# MM_Main.net
KiCad netlist of a schematic drawn in EAGLE
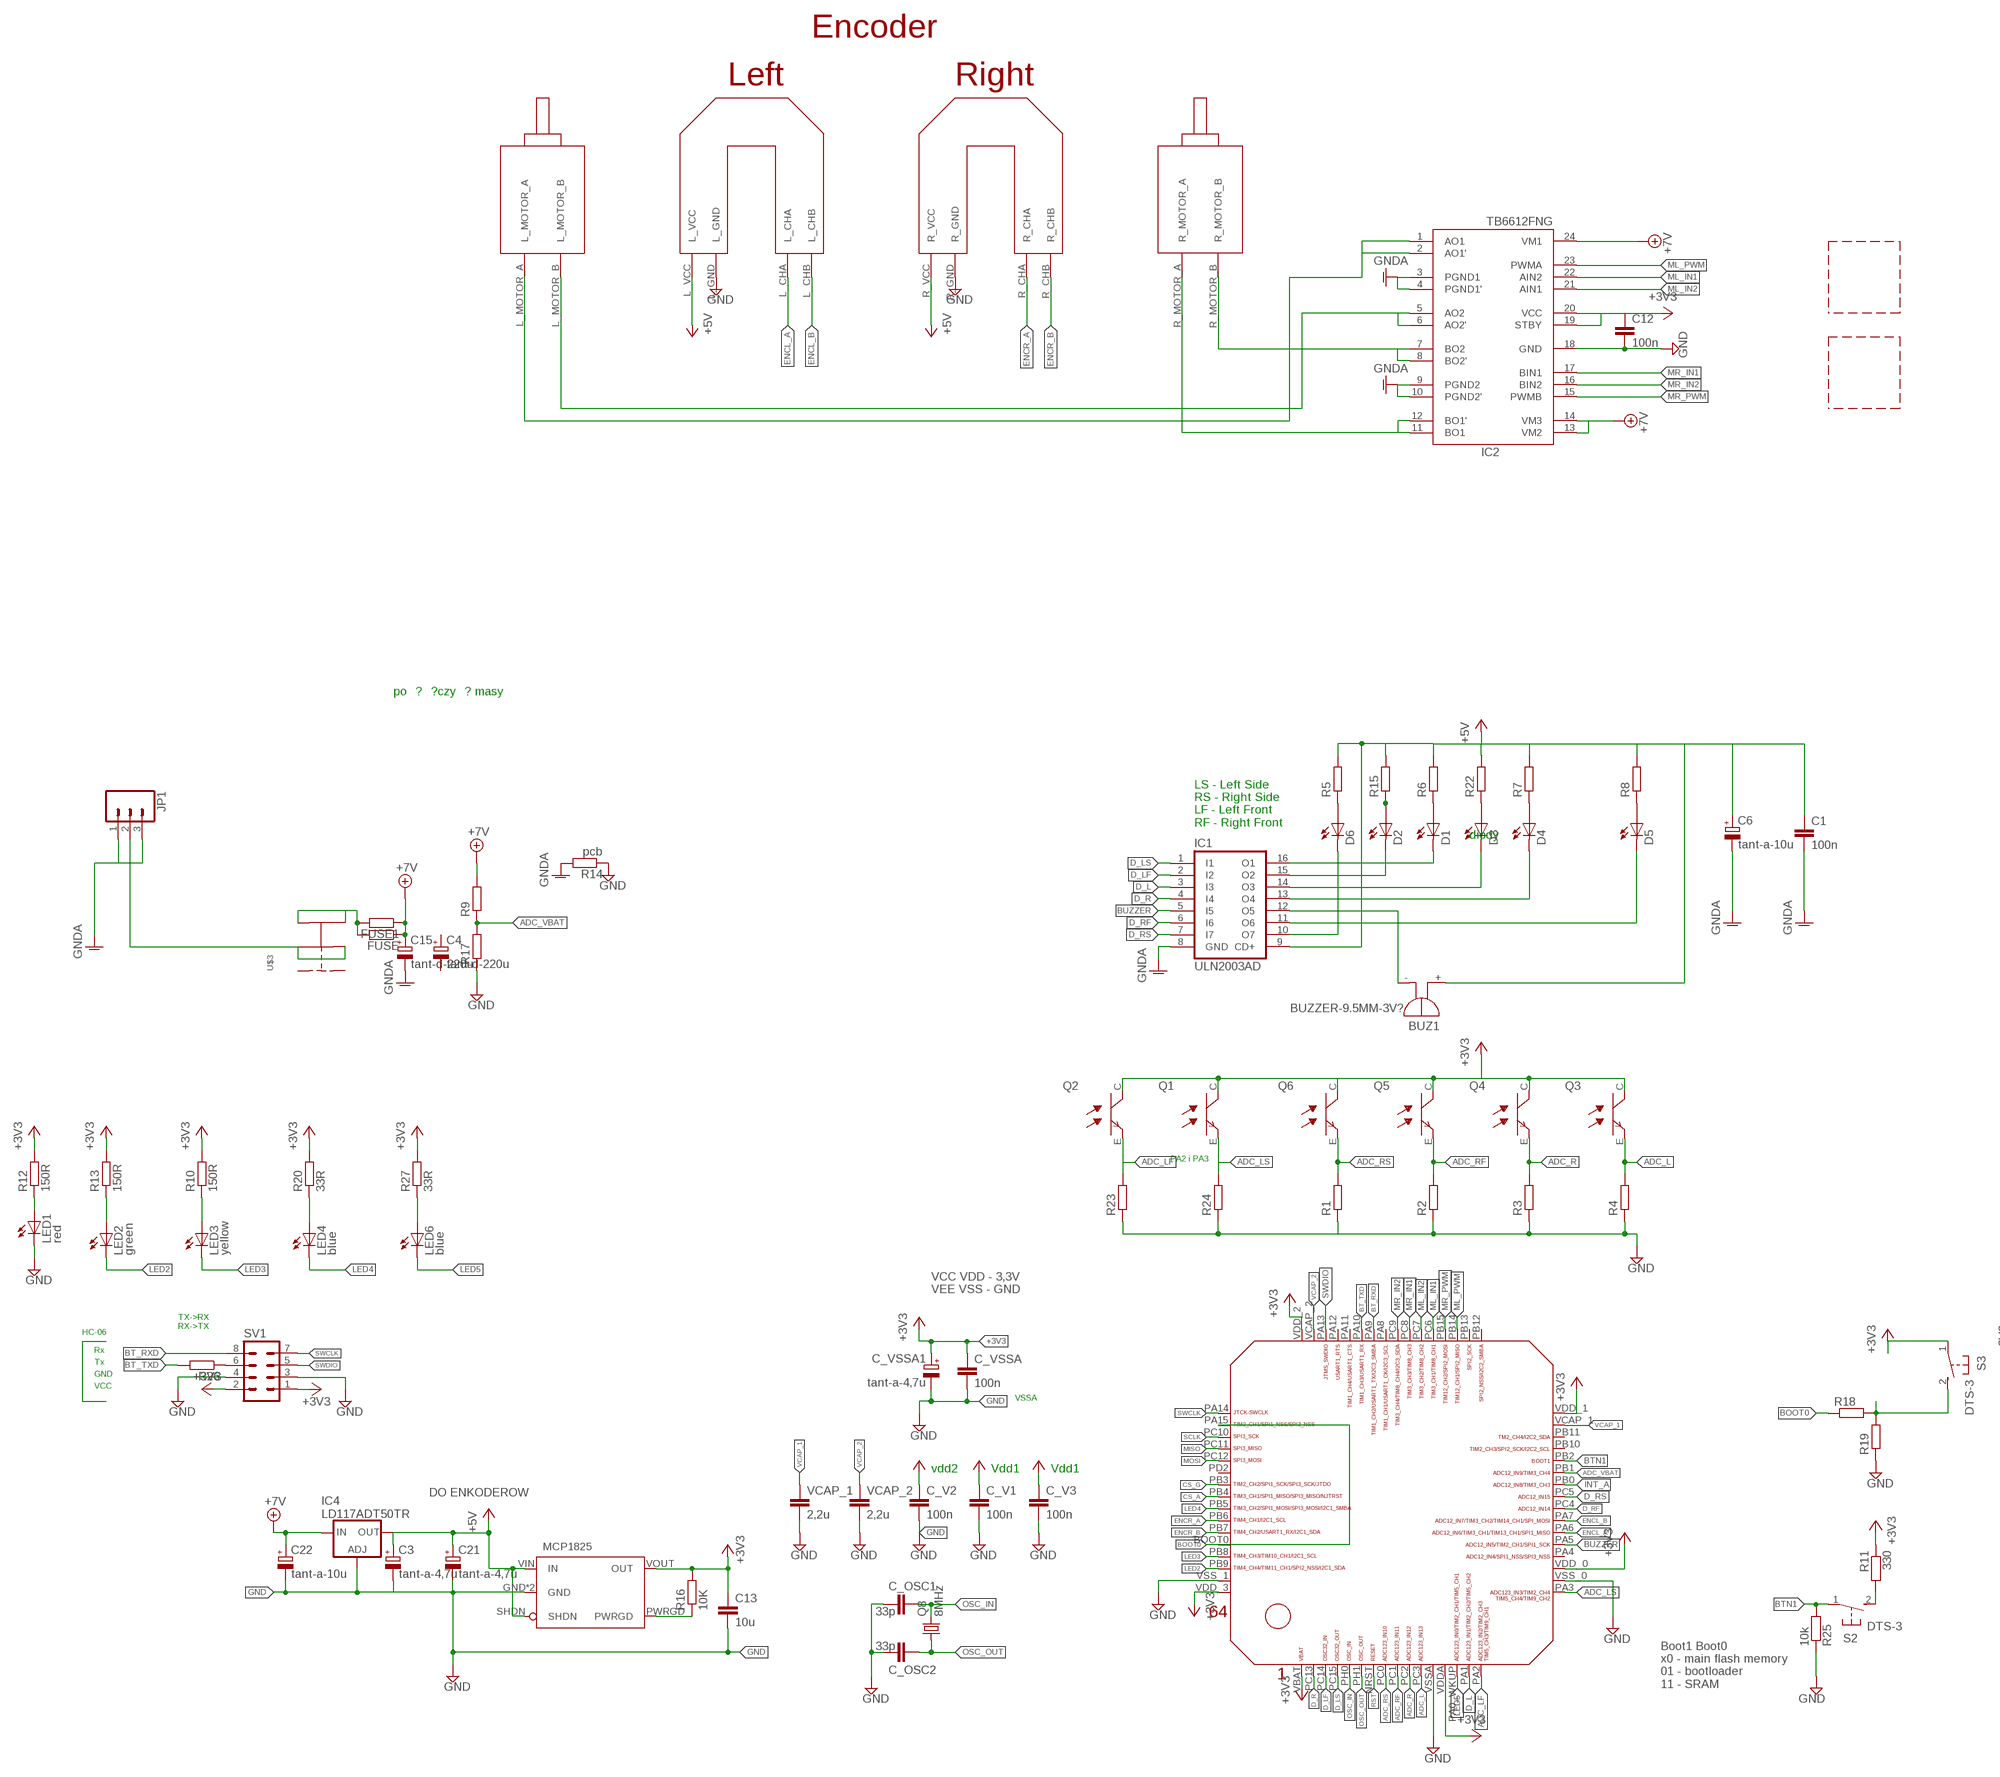
[diagram p0: schematic, sheet 1, part 1 of 2]
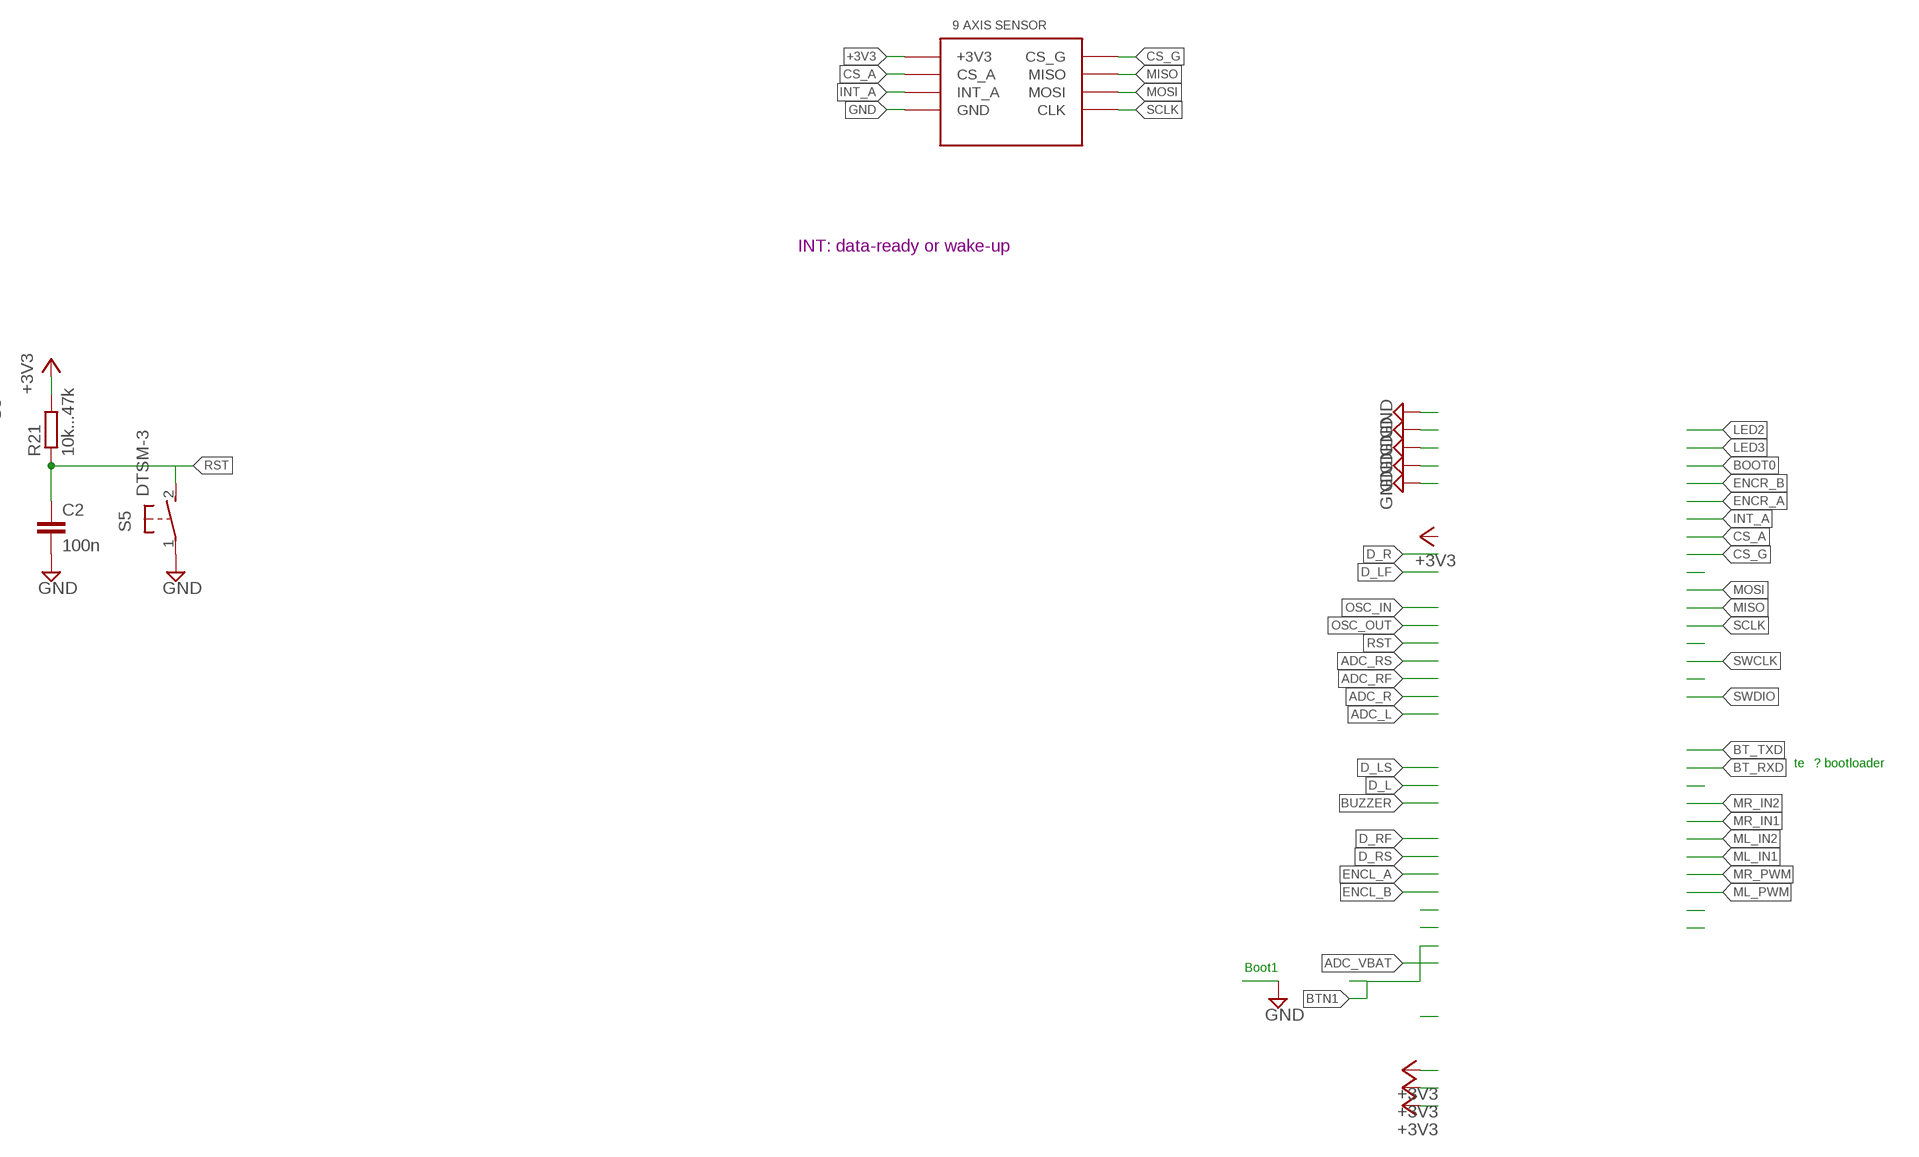
[diagram p1: schematic, sheet 1, part 2 of 2]

(export (version "E")
  (design (tool "Eeschema 10.0.6"))
  (components
    (comp (ref "BUZ1")
      (value "BUZZER-9.5MM-3V?")
      (footprint "eagle-import:BUZZER-9.5MM")
      (libsource (lib "eagle-import") (part "BUZZER-9.5MM"))
    )
    (comp (ref "C1")
      (value "100n")
      (footprint "eagle-import:C0805")
      (libsource (lib "eagle-import") (part "C-EUC0805"))
    )
    (comp (ref "C2")
      (value "100n")
      (footprint "eagle-import:C0805")
      (libsource (lib "eagle-import") (part "C-EUC0805"))
    )
    (comp (ref "C3")
      (value "tant-a-4,7u")
      (footprint "eagle-import:SMC_A")
      (libsource (lib "eagle-import") (part "CPOL-EUSMCA"))
    )
    (comp (ref "C4")
      (value "tant-d-220u")
      (footprint "eagle-import:SMC_D")
      (libsource (lib "eagle-import") (part "CPOL-EUSMCD"))
    )
    (comp (ref "C6")
      (value "tant-a-10u")
      (footprint "eagle-import:SMC_A")
      (libsource (lib "eagle-import") (part "CPOL-EUSMCA"))
    )
    (comp (ref "C12")
      (value "100n")
      (footprint "eagle-import:C0603")
      (libsource (lib "eagle-import") (part "C-EUC0603"))
    )
    (comp (ref "C13")
      (value "10u")
      (footprint "eagle-import:C0805")
      (libsource (lib "eagle-import") (part "C-EUC0805"))
    )
    (comp (ref "C15")
      (value "tant-d-220u")
      (footprint "eagle-import:SMC_D")
      (libsource (lib "eagle-import") (part "CPOL-EUSMCD"))
    )
    (comp (ref "C21")
      (value "tant-a-4,7u")
      (footprint "eagle-import:SMC_A")
      (libsource (lib "eagle-import") (part "CPOL-EUSMCA"))
    )
    (comp (ref "C22")
      (value "tant-a-10u")
      (footprint "eagle-import:SMC_A")
      (libsource (lib "eagle-import") (part "CPOL-EUSMCA"))
    )
    (comp (ref "C_OSC1")
      (value "33p")
      (footprint "eagle-import:C0805")
      (libsource (lib "eagle-import") (part "C-EUC0805"))
    )
    (comp (ref "C_OSC2")
      (value "33p")
      (footprint "eagle-import:C0805")
      (libsource (lib "eagle-import") (part "C-EUC0805"))
    )
    (comp (ref "C_V1")
      (value "100n")
      (footprint "eagle-import:C0805")
      (libsource (lib "eagle-import") (part "C-EUC0805"))
    )
    (comp (ref "C_V2")
      (value "100n")
      (footprint "eagle-import:C0805")
      (libsource (lib "eagle-import") (part "C-EUC0805"))
    )
    (comp (ref "C_V3")
      (value "100n")
      (footprint "eagle-import:C0805")
      (libsource (lib "eagle-import") (part "C-EUC0805"))
    )
    (comp (ref "C_VSSA")
      (value "100n")
      (footprint "eagle-import:C0805")
      (libsource (lib "eagle-import") (part "C-EUC0805"))
    )
    (comp (ref "C_VSSA1")
      (value "tant-a-4,7u")
      (footprint "eagle-import:SMC_A")
      (libsource (lib "eagle-import") (part "CPOL-EUSMCA"))
    )
    (comp (ref "D1")
      (value "SFH4545-C")
      (footprint "eagle-import:SFH4545-C")
      (libsource (lib "eagle-import") (part "SFH4545-C"))
    )
    (comp (ref "D2")
      (value "SFH4545-C")
      (footprint "eagle-import:SFH4545-C")
      (libsource (lib "eagle-import") (part "SFH4545-C"))
    )
    (comp (ref "D3")
      (value "SFH4545-C")
      (footprint "eagle-import:SFH4545-C")
      (libsource (lib "eagle-import") (part "SFH4545-C"))
    )
    (comp (ref "D4")
      (value "SFH4545-C")
      (footprint "eagle-import:SFH4545-C")
      (libsource (lib "eagle-import") (part "SFH4545-C"))
    )
    (comp (ref "D5")
      (value "SFH4545-C")
      (footprint "eagle-import:SFH4545-C")
      (libsource (lib "eagle-import") (part "SFH4545-C"))
    )
    (comp (ref "D6")
      (value "SFH4545-C")
      (footprint "eagle-import:SFH4545-C")
      (libsource (lib "eagle-import") (part "SFH4545-C"))
    )
    (comp (ref "FUSE")
      (value "R-EU_M3516")
      (footprint "eagle-import:M3516")
      (libsource (lib "eagle-import") (part "resistor_R-EU_M3516"))
    )
    (comp (ref "FUSE1")
      (value "R-EU_M3516")
      (footprint "eagle-import:M3516")
      (libsource (lib "eagle-import") (part "resistor_R-EU_M3516"))
    )
    (comp (ref "IC1")
      (value "ULN2003AD")
      (footprint "eagle-import:SO16")
      (libsource (lib "eagle-import") (part "ULN2003AD"))
    )
    (comp (ref "IC2")
      (value "TB6612FNG")
      (footprint "eagle-import:SSOP24")
      (libsource (lib "eagle-import") (part "TB6612FNG"))
    )
    (comp (ref "IC4")
      (value "LD117ADT50TR")
      (footprint "eagle-import:DPACK")
      (libsource (lib "eagle-import") (part "LD117A?DT50TR"))
    )
    (comp (ref "IC5")
      (value "MCP1825")
      (footprint "eagle-import:SOT223-5")
      (libsource (lib "eagle-import") (part "MCP1825"))
    )
    (comp (ref "JP1")
      (value "M03POLAR")
      (footprint "eagle-import:MOLEX-1X3")
      (libsource (lib "eagle-import") (part "M03POLAR"))
    )
    (comp (ref "L1")
      (value "LABITYNT")
      (footprint "eagle-import:LABIRYNT")
      (libsource (lib "eagle-import") (part "LABITYNT"))
    )
    (comp (ref "L2")
      (value "LABITYNT")
      (footprint "eagle-import:LABIRYNT")
      (libsource (lib "eagle-import") (part "LABITYNT"))
    )
    (comp (ref "LED1")
      (value "red")
      (footprint "eagle-import:SML1206")
      (libsource (lib "eagle-import") (part "LEDSML1206"))
    )
    (comp (ref "LED2")
      (value "green")
      (footprint "eagle-import:SML1206")
      (libsource (lib "eagle-import") (part "LEDSML1206"))
    )
    (comp (ref "LED3")
      (value "yellow")
      (footprint "eagle-import:SML1206")
      (libsource (lib "eagle-import") (part "LEDSML1206"))
    )
    (comp (ref "LED4")
      (value "blue")
      (footprint "eagle-import:SML1206")
      (libsource (lib "eagle-import") (part "LEDSML1206"))
    )
    (comp (ref "LED6")
      (value "blue")
      (footprint "eagle-import:SML1206")
      (libsource (lib "eagle-import") (part "LEDSML1206"))
    )
    (comp (ref "Q1")
      (value "TEFT4300")
      (footprint "eagle-import:TEFT4300")
      (libsource (lib "eagle-import") (part "TEFT4300"))
    )
    (comp (ref "Q2")
      (value "TEFT4300")
      (footprint "eagle-import:TEFT4300")
      (libsource (lib "eagle-import") (part "TEFT4300"))
    )
    (comp (ref "Q3")
      (value "TEFT4300")
      (footprint "eagle-import:TEFT4300")
      (libsource (lib "eagle-import") (part "TEFT4300"))
    )
    (comp (ref "Q4")
      (value "TEFT4300")
      (footprint "eagle-import:TEFT4300")
      (libsource (lib "eagle-import") (part "TEFT4300"))
    )
    (comp (ref "Q5")
      (value "TEFT4300")
      (footprint "eagle-import:TEFT4300")
      (libsource (lib "eagle-import") (part "TEFT4300"))
    )
    (comp (ref "Q6")
      (value "TEFT4300")
      (footprint "eagle-import:TEFT4300")
      (libsource (lib "eagle-import") (part "TEFT4300"))
    )
    (comp (ref "Q8")
      (value "8MHz")
      (footprint "eagle-import:CRYSTAL_5X3.2MM")
      (libsource (lib "eagle-import") (part "CRYSTAL_5X3.2MM"))
    )
    (comp (ref "R1")
      (value "R-EU_R0805")
      (footprint "eagle-import:R0805")
      (libsource (lib "eagle-import") (part "R-EU_R0805"))
    )
    (comp (ref "R2")
      (value "R-EU_R0805")
      (footprint "eagle-import:R0805")
      (libsource (lib "eagle-import") (part "R-EU_R0805"))
    )
    (comp (ref "R3")
      (value "R-EU_R0805")
      (footprint "eagle-import:R0805")
      (libsource (lib "eagle-import") (part "R-EU_R0805"))
    )
    (comp (ref "R4")
      (value "R-EU_R0805")
      (footprint "eagle-import:R0805")
      (libsource (lib "eagle-import") (part "R-EU_R0805"))
    )
    (comp (ref "R5")
      (value "R-EU_R0805")
      (footprint "eagle-import:R0805")
      (libsource (lib "eagle-import") (part "R-EU_R0805"))
    )
    (comp (ref "R6")
      (value "R-EU_R0805")
      (footprint "eagle-import:R0805")
      (libsource (lib "eagle-import") (part "R-EU_R0805"))
    )
    (comp (ref "R7")
      (value "R-EU_R0805")
      (footprint "eagle-import:R0805")
      (libsource (lib "eagle-import") (part "R-EU_R0805"))
    )
    (comp (ref "R8")
      (value "R-EU_R0805")
      (footprint "eagle-import:R0805")
      (libsource (lib "eagle-import") (part "R-EU_R0805"))
    )
    (comp (ref "R9")
      (value "R-EU_R0805")
      (footprint "eagle-import:R0805")
      (libsource (lib "eagle-import") (part "resistor_R-EU_R0805"))
    )
    (comp (ref "R10")
      (value "150R")
      (footprint "eagle-import:R0805")
      (libsource (lib "eagle-import") (part "resistor_R-EU_R0805"))
    )
    (comp (ref "R11")
      (value "330")
      (footprint "eagle-import:R0805")
      (libsource (lib "eagle-import") (part "resistor_R-EU_R0805"))
    )
    (comp (ref "R12")
      (value "150R")
      (footprint "eagle-import:R0805")
      (libsource (lib "eagle-import") (part "resistor_R-EU_R0805"))
    )
    (comp (ref "R13")
      (value "150R")
      (footprint "eagle-import:R0805")
      (libsource (lib "eagle-import") (part "resistor_R-EU_R0805"))
    )
    (comp (ref "R14")
      (value "pcb")
      (footprint "eagle-import:R0201")
      (libsource (lib "eagle-import") (part "resistor_R-EU_R0201"))
    )
    (comp (ref "R15")
      (value "R-EU_R0805")
      (footprint "eagle-import:R0805")
      (libsource (lib "eagle-import") (part "R-EU_R0805"))
    )
    (comp (ref "R16")
      (value "10K")
      (footprint "eagle-import:R0805")
      (libsource (lib "eagle-import") (part "resistor_R-EU_R0805"))
    )
    (comp (ref "R17")
      (value "R-EU_R0805")
      (footprint "eagle-import:R0805")
      (libsource (lib "eagle-import") (part "resistor_R-EU_R0805"))
    )
    (comp (ref "R18")
      (value "R-EU_R0805")
      (footprint "eagle-import:R0805")
      (libsource (lib "eagle-import") (part "R-EU_R0805"))
    )
    (comp (ref "R19")
      (value "R-EU_R0805")
      (footprint "eagle-import:R0805")
      (libsource (lib "eagle-import") (part "R-EU_R0805"))
    )
    (comp (ref "R20")
      (value "33R")
      (footprint "eagle-import:R0805")
      (libsource (lib "eagle-import") (part "resistor_R-EU_R0805"))
    )
    (comp (ref "R21")
      (value "10k...47k")
      (footprint "eagle-import:R0805")
      (libsource (lib "eagle-import") (part "R-EU_R0805"))
    )
    (comp (ref "R22")
      (value "R-EU_R0805")
      (footprint "eagle-import:R0805")
      (libsource (lib "eagle-import") (part "R-EU_R0805"))
    )
    (comp (ref "R23")
      (value "R-EU_R0805")
      (footprint "eagle-import:R0805")
      (libsource (lib "eagle-import") (part "R-EU_R0805"))
    )
    (comp (ref "R24")
      (value "R-EU_R0805")
      (footprint "eagle-import:R0805")
      (libsource (lib "eagle-import") (part "R-EU_R0805"))
    )
    (comp (ref "R25")
      (value "10k")
      (footprint "eagle-import:R0805")
      (libsource (lib "eagle-import") (part "R-EU_R0805"))
    )
    (comp (ref "R26")
      (value "R-EU_R0805")
      (footprint "eagle-import:R0805")
      (libsource (lib "eagle-import") (part "R-EU_R0805"))
    )
    (comp (ref "R27")
      (value "33R")
      (footprint "eagle-import:R0805")
      (libsource (lib "eagle-import") (part "resistor_R-EU_R0805"))
    )
    (comp (ref "S2")
      (value "DTS-3")
      (footprint "eagle-import:DTS-3")
      (libsource (lib "eagle-import") (part "DTS-3"))
    )
    (comp (ref "S3")
      (value "DTS-3")
      (footprint "eagle-import:DTS-3")
      (libsource (lib "eagle-import") (part "DTS-3"))
    )
    (comp (ref "S5")
      (value "DTSM-3")
      (footprint "eagle-import:DTSM-3")
      (libsource (lib "eagle-import") (part "DTSM-3"))
    )
    (comp (ref "SV1")
      (value "MA04-2")
      (footprint "eagle-import:MA04-2")
      (libsource (lib "eagle-import") (part "MA04-2"))
    )
    (comp (ref "U$1")
      (value "9AXIS_MODULE")
      (footprint "eagle-import:9AXIS_SENSOR_MODULE")
      (libsource (lib "eagle-import") (part "9AXIS_MODULE"))
    )
    (comp (ref "U$3")
      (value "PRZELACZNIK_SUWAKOWY")
      (footprint "eagle-import:PRZELACZNIK_SUWAKOWY")
      (libsource (lib "eagle-import") (part "PRZELACZNIK_SUWAKOWY"))
    )
    (comp (ref "U$5")
      (value "MOTOR_MOUNT")
      (footprint "eagle-import:MOTOR_MOUNT")
      (libsource (lib "eagle-import") (part "MOTOR_MOUNT"))
    )
    (comp (ref "U$6")
      (value "STM32F4X5")
      (footprint "eagle-import:STM32F4-LQFP64")
      (libsource (lib "eagle-import") (part "STM32F4X5"))
    )
    (comp (ref "VCAP_1")
      (value "2,2u")
      (footprint "eagle-import:C0805")
      (libsource (lib "eagle-import") (part "C-EUC0805"))
    )
    (comp (ref "VCAP_2")
      (value "2,2u")
      (footprint "eagle-import:C0805")
      (libsource (lib "eagle-import") (part "C-EUC0805"))
    )
  )
  (nets
    (net (code "1") (name "+3V3") (class "Default")
      (node (ref "C12") (pin "1") (pinfunction "1_1") (pintype "passive"))
      (node (ref "C13") (pin "1") (pinfunction "1_1") (pintype "passive"))
      (node (ref "C_V1") (pin "1") (pinfunction "1_1") (pintype "passive"))
      (node (ref "C_V2") (pin "1") (pinfunction "1_1") (pintype "passive"))
      (node (ref "C_V3") (pin "1") (pinfunction "1_1") (pintype "passive"))
      (node (ref "C_VSSA") (pin "1") (pinfunction "1_1") (pintype "passive"))
      (node (ref "C_VSSA1") (pin "+") (pinfunction "+_+") (pintype "passive"))
      (node (ref "IC2") (pin "19") (pinfunction "STBY_19") (pintype "input"))
      (node (ref "IC2") (pin "20") (pinfunction "VCC_20") (pintype "power_in"))
      (node (ref "IC5") (pin "VOUT") (pinfunction "OUT_VOUT") (pintype "bidirectional"))
      (node (ref "Q1") (pin "C") (pinfunction "C_C") (pintype "bidirectional"))
      (node (ref "Q2") (pin "C") (pinfunction "C_C") (pintype "bidirectional"))
      (node (ref "Q3") (pin "C") (pinfunction "C_C") (pintype "bidirectional"))
      (node (ref "Q4") (pin "C") (pinfunction "C_C") (pintype "bidirectional"))
      (node (ref "Q5") (pin "C") (pinfunction "C_C") (pintype "bidirectional"))
      (node (ref "Q6") (pin "C") (pinfunction "C_C") (pintype "bidirectional"))
      (node (ref "R10") (pin "2") (pinfunction "2_2") (pintype "passive"))
      (node (ref "R11") (pin "1") (pinfunction "1_1") (pintype "passive"))
      (node (ref "R12") (pin "2") (pinfunction "2_2") (pintype "passive"))
      (node (ref "R13") (pin "2") (pinfunction "2_2") (pintype "passive"))
      (node (ref "R16") (pin "2") (pinfunction "2_2") (pintype "passive"))
      (node (ref "R20") (pin "2") (pinfunction "2_2") (pintype "passive"))
      (node (ref "R21") (pin "2") (pinfunction "2_2") (pintype "passive"))
      (node (ref "R27") (pin "2") (pinfunction "2_2") (pintype "passive"))
      (node (ref "S3") (pin "1") (pinfunction "1_1") (pintype "passive"))
      (node (ref "SV1") (pin "1") (pinfunction "1_1") (pintype "passive"))
      (node (ref "SV1") (pin "2") (pinfunction "2_2") (pintype "passive"))
      (node (ref "U$1") (pin "P$1") (pinfunction "+3V3_P$1") (pintype "output"))
      (node (ref "U$6") (pin "VBAT") (pinfunction "VBAT_VBAT") (pintype "bidirectional"))
      (node (ref "U$6") (pin "VDDA") (pinfunction "VDDA_VDDA") (pintype "bidirectional"))
      (node (ref "U$6") (pin "VDD_0") (pinfunction "VDD_0_VDD_0") (pintype "bidirectional"))
      (node (ref "U$6") (pin "VDD_1") (pinfunction "VDD_1_VDD_1") (pintype "bidirectional"))
      (node (ref "U$6") (pin "VDD_2") (pinfunction "VDD_2_VDD_2") (pintype "bidirectional"))
      (node (ref "U$6") (pin "VDD_3") (pinfunction "VDD_3_VDD_3") (pintype "bidirectional"))
    )
    (net (code "2") (name "+5V") (class "Default")
      (node (ref "BUZ1") (pin "+") (pinfunction "+_+") (pintype "passive"))
      (node (ref "C1") (pin "1") (pinfunction "1_1") (pintype "passive"))
      (node (ref "C21") (pin "+") (pinfunction "+_+") (pintype "passive"))
      (node (ref "C3") (pin "+") (pinfunction "+_+") (pintype "passive"))
      (node (ref "C6") (pin "+") (pinfunction "+_+") (pintype "passive"))
      (node (ref "IC1") (pin "9") (pinfunction "CD+_9") (pintype "passive"))
      (node (ref "IC4") (pin "4") (pinfunction "OUT_4") (pintype "passive"))
      (node (ref "IC5") (pin "SHDN") (pinfunction "SHDN_SHDN") (pintype "bidirectional"))
      (node (ref "IC5") (pin "VIN") (pinfunction "IN_VIN") (pintype "bidirectional"))
      (node (ref "R15") (pin "2") (pinfunction "2_2") (pintype "passive"))
      (node (ref "R22") (pin "2") (pinfunction "2_2") (pintype "passive"))
      (node (ref "R5") (pin "2") (pinfunction "2_2") (pintype "passive"))
      (node (ref "R6") (pin "2") (pinfunction "2_2") (pintype "passive"))
      (node (ref "R7") (pin "2") (pinfunction "2_2") (pintype "passive"))
      (node (ref "R8") (pin "2") (pinfunction "2_2") (pintype "passive"))
      (node (ref "U$5") (pin "L_VCC") (pinfunction "L_VCC_L_VCC") (pintype "bidirectional"))
      (node (ref "U$5") (pin "R_VCC") (pinfunction "R_VCC_R_VCC") (pintype "bidirectional"))
    )
    (net (code "3") (name "+7V") (class "Default")
      (node (ref "C15") (pin "+") (pinfunction "+_+") (pintype "passive"))
      (node (ref "C22") (pin "+") (pinfunction "+_+") (pintype "passive"))
      (node (ref "FUSE") (pin "1") (pinfunction "1_1") (pintype "passive"))
      (node (ref "FUSE1") (pin "1") (pinfunction "1_1") (pintype "passive"))
      (node (ref "IC2") (pin "13") (pinfunction "VM2_13") (pintype "power_in"))
      (node (ref "IC2") (pin "14") (pinfunction "VM3_14") (pintype "power_in"))
      (node (ref "IC2") (pin "24") (pinfunction "VM1_24") (pintype "power_in"))
      (node (ref "IC4") (pin "3") (pinfunction "IN_3") (pintype "input"))
      (node (ref "R9") (pin "2") (pinfunction "2_2") (pintype "passive"))
    )
    (net (code "4") (name "ADC_L") (class "Default")
      (node (ref "Q3") (pin "E") (pinfunction "E_E") (pintype "bidirectional"))
      (node (ref "R4") (pin "2") (pinfunction "2_2") (pintype "passive"))
      (node (ref "U$6") (pin "PC3") (pinfunction "PC3_PC3") (pintype "bidirectional"))
    )
    (net (code "5") (name "ADC_LF") (class "Default")
      (node (ref "Q2") (pin "E") (pinfunction "E_E") (pintype "bidirectional"))
      (node (ref "R23") (pin "2") (pinfunction "2_2") (pintype "passive"))
      (node (ref "U$6") (pin "PA2") (pinfunction "PA2_PA2") (pintype "bidirectional"))
    )
    (net (code "6") (name "ADC_LS") (class "Default")
      (node (ref "Q1") (pin "E") (pinfunction "E_E") (pintype "bidirectional"))
      (node (ref "R24") (pin "2") (pinfunction "2_2") (pintype "passive"))
      (node (ref "U$6") (pin "PA3") (pinfunction "PA3_PA3") (pintype "bidirectional"))
    )
    (net (code "7") (name "ADC_R") (class "Default")
      (node (ref "Q4") (pin "E") (pinfunction "E_E") (pintype "bidirectional"))
      (node (ref "R3") (pin "2") (pinfunction "2_2") (pintype "passive"))
      (node (ref "U$6") (pin "PC2") (pinfunction "PC2_PC2") (pintype "bidirectional"))
    )
    (net (code "8") (name "ADC_RF") (class "Default")
      (node (ref "Q5") (pin "E") (pinfunction "E_E") (pintype "bidirectional"))
      (node (ref "R2") (pin "2") (pinfunction "2_2") (pintype "passive"))
      (node (ref "U$6") (pin "PC1") (pinfunction "PC1_PC1") (pintype "bidirectional"))
    )
    (net (code "9") (name "ADC_RS") (class "Default")
      (node (ref "Q6") (pin "E") (pinfunction "E_E") (pintype "bidirectional"))
      (node (ref "R1") (pin "2") (pinfunction "2_2") (pintype "passive"))
      (node (ref "U$6") (pin "PC0") (pinfunction "PC0_PC0") (pintype "bidirectional"))
    )
    (net (code "10") (name "ADC_VBAT") (class "Default")
      (node (ref "R17") (pin "2") (pinfunction "2_2") (pintype "passive"))
      (node (ref "R9") (pin "1") (pinfunction "1_1") (pintype "passive"))
      (node (ref "U$6") (pin "PB1") (pinfunction "PB1_PB1") (pintype "bidirectional"))
    )
    (net (code "11") (name "BOOT0") (class "Default")
      (node (ref "R18") (pin "1") (pinfunction "1_1") (pintype "passive"))
      (node (ref "U$6") (pin "BOOT0") (pinfunction "BOOT0_BOOT0") (pintype "bidirectional"))
      (node (ref "U$6") (pin "PA15") (pinfunction "PA15_PA15") (pintype "bidirectional"))
    )
    (net (code "12") (name "BTN1") (class "Default")
      (node (ref "R25") (pin "2") (pinfunction "2_2") (pintype "passive"))
      (node (ref "S2") (pin "1") (pinfunction "1_1") (pintype "passive"))
      (node (ref "U$6") (pin "PB2") (pinfunction "PB2_PB2") (pintype "bidirectional"))
    )
    (net (code "13") (name "BT_RXD") (class "Default")
      (node (ref "SV1") (pin "8") (pinfunction "8_8") (pintype "passive"))
      (node (ref "U$6") (pin "PA9") (pinfunction "PA9_PA9") (pintype "bidirectional"))
    )
    (net (code "14") (name "BT_TXD") (class "Default")
      (node (ref "R26") (pin "2") (pinfunction "2_2") (pintype "passive"))
      (node (ref "U$6") (pin "PA10") (pinfunction "PA10_PA10") (pintype "bidirectional"))
    )
    (net (code "15") (name "BUZZER") (class "Default")
      (node (ref "IC1") (pin "5") (pinfunction "I5_5") (pintype "input"))
      (node (ref "U$6") (pin "PA5") (pinfunction "PA5_PA5") (pintype "bidirectional"))
    )
    (net (code "16") (name "CS_A") (class "Default")
      (node (ref "U$1") (pin "P$2") (pinfunction "CS_A_P$2") (pintype "power_in"))
      (node (ref "U$6") (pin "PB4") (pinfunction "PB4_PB4") (pintype "bidirectional"))
    )
    (net (code "17") (name "CS_G") (class "Default")
      (node (ref "U$1") (pin "P$8") (pinfunction "CS_G_P$8") (pintype "output"))
      (node (ref "U$6") (pin "PB3") (pinfunction "PB3_PB3") (pintype "bidirectional"))
    )
    (net (code "18") (name "D_L") (class "Default")
      (node (ref "IC1") (pin "3") (pinfunction "I3_3") (pintype "input"))
      (node (ref "U$6") (pin "PA1") (pinfunction "PA1_PA1") (pintype "bidirectional"))
    )
    (net (code "19") (name "D_LF") (class "Default")
      (node (ref "IC1") (pin "2") (pinfunction "I2_2") (pintype "input"))
      (node (ref "U$6") (pin "PC14") (pinfunction "PC14_PC14") (pintype "bidirectional"))
    )
    (net (code "20") (name "D_LS") (class "Default")
      (node (ref "IC1") (pin "1") (pinfunction "I1_1") (pintype "input"))
      (node (ref "U$6") (pin "PC15") (pinfunction "PC15_PC15") (pintype "bidirectional"))
    )
    (net (code "21") (name "D_R") (class "Default")
      (node (ref "IC1") (pin "4") (pinfunction "I4_4") (pintype "input"))
      (node (ref "U$6") (pin "PC13") (pinfunction "PC13_PC13") (pintype "bidirectional"))
    )
    (net (code "22") (name "D_RF") (class "Default")
      (node (ref "IC1") (pin "6") (pinfunction "I6_6") (pintype "input"))
      (node (ref "U$6") (pin "PC4") (pinfunction "PC4_PC4") (pintype "bidirectional"))
    )
    (net (code "23") (name "D_RS") (class "Default")
      (node (ref "IC1") (pin "7") (pinfunction "I7_7") (pintype "input"))
      (node (ref "U$6") (pin "PC5") (pinfunction "PC5_PC5") (pintype "bidirectional"))
    )
    (net (code "24") (name "ENCL_A") (class "Default")
      (node (ref "U$5") (pin "L_CHA") (pinfunction "L_CHA_L_CHA") (pintype "bidirectional"))
      (node (ref "U$6") (pin "PA6") (pinfunction "PA6_PA6") (pintype "bidirectional"))
    )
    (net (code "25") (name "ENCL_B") (class "Default")
      (node (ref "U$5") (pin "L_CHB") (pinfunction "L_CHB_L_CHB") (pintype "bidirectional"))
      (node (ref "U$6") (pin "PA7") (pinfunction "PA7_PA7") (pintype "bidirectional"))
    )
    (net (code "26") (name "ENCR_A") (class "Default")
      (node (ref "U$5") (pin "R_CHA") (pinfunction "R_CHA_R_CHA") (pintype "bidirectional"))
      (node (ref "U$6") (pin "PB6") (pinfunction "PB6_PB6") (pintype "bidirectional"))
    )
    (net (code "27") (name "ENCR_B") (class "Default")
      (node (ref "U$5") (pin "R_CHB") (pinfunction "R_CHB_R_CHB") (pintype "bidirectional"))
      (node (ref "U$6") (pin "PB7") (pinfunction "PB7_PB7") (pintype "bidirectional"))
    )
    (net (code "28") (name "GND") (class "Default")
      (node (ref "C12") (pin "2") (pinfunction "2_2") (pintype "passive"))
      (node (ref "C13") (pin "2") (pinfunction "2_2") (pintype "passive"))
      (node (ref "C2") (pin "2") (pinfunction "2_2") (pintype "passive"))
      (node (ref "C21") (pin "-") (pinfunction "-_-") (pintype "passive"))
      (node (ref "C22") (pin "-") (pinfunction "-_-") (pintype "passive"))
      (node (ref "C3") (pin "-") (pinfunction "-_-") (pintype "passive"))
      (node (ref "C_OSC1") (pin "1") (pinfunction "1_1") (pintype "passive"))
      (node (ref "C_OSC2") (pin "1") (pinfunction "1_1") (pintype "passive"))
      (node (ref "C_V1") (pin "2") (pinfunction "2_2") (pintype "passive"))
      (node (ref "C_V2") (pin "2") (pinfunction "2_2") (pintype "passive"))
      (node (ref "C_V3") (pin "2") (pinfunction "2_2") (pintype "passive"))
      (node (ref "C_VSSA") (pin "2") (pinfunction "2_2") (pintype "passive"))
      (node (ref "C_VSSA1") (pin "-") (pinfunction "-_-") (pintype "passive"))
      (node (ref "IC2") (pin "18") (pinfunction "GND_18") (pintype "power_in"))
      (node (ref "IC4") (pin "1") (pinfunction "ADJ_1") (pintype "input"))
      (node (ref "IC5") (pin "GND") (pinfunction "GND_GND") (pintype "bidirectional"))
      (node (ref "IC5") (pin "GND_TAB") (pinfunction "GND_GND_TAB") (pintype "bidirectional"))
      (node (ref "LED1") (pin "C") (pinfunction "C_C") (pintype "passive"))
      (node (ref "R1") (pin "1") (pinfunction "1_1") (pintype "passive"))
      (node (ref "R14") (pin "1") (pinfunction "1_1") (pintype "passive"))
      (node (ref "R17") (pin "1") (pinfunction "1_1") (pintype "passive"))
      (node (ref "R19") (pin "1") (pinfunction "1_1") (pintype "passive"))
      (node (ref "R2") (pin "1") (pinfunction "1_1") (pintype "passive"))
      (node (ref "R23") (pin "1") (pinfunction "1_1") (pintype "passive"))
      (node (ref "R24") (pin "1") (pinfunction "1_1") (pintype "passive"))
      (node (ref "R25") (pin "1") (pinfunction "1_1") (pintype "passive"))
      (node (ref "R3") (pin "1") (pinfunction "1_1") (pintype "passive"))
      (node (ref "R4") (pin "1") (pinfunction "1_1") (pintype "passive"))
      (node (ref "S5") (pin "1") (pinfunction "1_1") (pintype "passive"))
      (node (ref "SV1") (pin "3") (pinfunction "3_3") (pintype "passive"))
      (node (ref "SV1") (pin "4") (pinfunction "4_4") (pintype "passive"))
      (node (ref "U$1") (pin "P$4") (pinfunction "GND_P$4") (pintype "input"))
      (node (ref "U$5") (pin "L_GND") (pinfunction "L_GND_L_GND") (pintype "bidirectional"))
      (node (ref "U$5") (pin "R_GND") (pinfunction "R_GND_R_GND") (pintype "bidirectional"))
      (node (ref "U$6") (pin "VSSA") (pinfunction "VSSA_VSSA") (pintype "bidirectional"))
      (node (ref "U$6") (pin "VSS_0") (pinfunction "VSS_0_VSS_0") (pintype "bidirectional"))
      (node (ref "U$6") (pin "VSS_1") (pinfunction "VSS_1_VSS_1") (pintype "bidirectional"))
      (node (ref "VCAP_1") (pin "2") (pinfunction "2_2") (pintype "passive"))
      (node (ref "VCAP_2") (pin "2") (pinfunction "2_2") (pintype "passive"))
    )
    (net (code "29") (name "GNDA") (class "Default")
      (node (ref "C1") (pin "2") (pinfunction "2_2") (pintype "passive"))
      (node (ref "C15") (pin "-") (pinfunction "-_-") (pintype "passive"))
      (node (ref "C6") (pin "-") (pinfunction "-_-") (pintype "passive"))
      (node (ref "IC1") (pin "8") (pinfunction "GND_8") (pintype "power_in"))
      (node (ref "IC2") (pin "10") (pinfunction "PGND2'_10") (pintype "power_in"))
      (node (ref "IC2") (pin "3") (pinfunction "PGND1_3") (pintype "power_in"))
      (node (ref "IC2") (pin "4") (pinfunction "PGND1'_4") (pintype "power_in"))
      (node (ref "IC2") (pin "9") (pinfunction "PGND2_9") (pintype "power_in"))
      (node (ref "JP1") (pin "1") (pinfunction "1_1") (pintype "passive"))
      (node (ref "JP1") (pin "3") (pinfunction "3_3") (pintype "passive"))
      (node (ref "R14") (pin "2") (pinfunction "2_2") (pintype "passive"))
    )
    (net (code "30") (name "INT_A") (class "Default")
      (node (ref "U$1") (pin "P$3") (pinfunction "INT_A_P$3") (pintype "power_in"))
      (node (ref "U$6") (pin "PB0") (pinfunction "PB0_PB0") (pintype "bidirectional"))
    )
    (net (code "31") (name "LED2") (class "Default")
      (node (ref "LED2") (pin "C") (pinfunction "C_C") (pintype "passive"))
      (node (ref "U$6") (pin "PB9") (pinfunction "PB9_PB9") (pintype "bidirectional"))
    )
    (net (code "32") (name "LED3") (class "Default")
      (node (ref "LED3") (pin "C") (pinfunction "C_C") (pintype "passive"))
      (node (ref "U$6") (pin "PB8") (pinfunction "PB8_PB8") (pintype "bidirectional"))
    )
    (net (code "33") (name "LED4") (class "Default")
      (node (ref "LED4") (pin "C") (pinfunction "C_C") (pintype "passive"))
      (node (ref "U$6") (pin "PB5") (pinfunction "PB5_PB5") (pintype "bidirectional"))
    )
    (net (code "34") (name "LED5") (class "Default")
      (node (ref "LED6") (pin "C") (pinfunction "C_C") (pintype "passive"))
      (node (ref "U$6") (pin "PA0_WKUP") (pinfunction "PA0_AKUP_PA0_WKUP") (pintype "bidirectional"))
    )
    (net (code "35") (name "MISO") (class "Default")
      (node (ref "U$1") (pin "P$7") (pinfunction "MISO_P$7") (pintype "input"))
      (node (ref "U$6") (pin "PC11") (pinfunction "PC11_PC11") (pintype "bidirectional"))
    )
    (net (code "36") (name "ML_IN1") (class "Default")
      (node (ref "IC2") (pin "22") (pinfunction "AIN2_22") (pintype "input"))
      (node (ref "U$6") (pin "PC6") (pinfunction "PC6_PC6") (pintype "bidirectional"))
    )
    (net (code "37") (name "ML_IN2") (class "Default")
      (node (ref "IC2") (pin "21") (pinfunction "AIN1_21") (pintype "input"))
      (node (ref "U$6") (pin "PC7") (pinfunction "PC7_PC7") (pintype "bidirectional"))
    )
    (net (code "38") (name "ML_PWM") (class "Default")
      (node (ref "IC2") (pin "23") (pinfunction "PWMA_23") (pintype "input"))
      (node (ref "U$6") (pin "PB14") (pinfunction "PB14_PB14") (pintype "bidirectional"))
    )
    (net (code "39") (name "MOSI") (class "Default")
      (node (ref "U$1") (pin "P$6") (pinfunction "MOSI_P$6") (pintype "input"))
      (node (ref "U$6") (pin "PC12") (pinfunction "PC12_PC12") (pintype "bidirectional"))
    )
    (net (code "40") (name "MR_IN1") (class "Default")
      (node (ref "IC2") (pin "17") (pinfunction "BIN1_17") (pintype "input"))
      (node (ref "U$6") (pin "PC8") (pinfunction "PC8_PC8") (pintype "bidirectional"))
    )
    (net (code "41") (name "MR_IN2") (class "Default")
      (node (ref "IC2") (pin "16") (pinfunction "BIN2_16") (pintype "input"))
      (node (ref "U$6") (pin "PC9") (pinfunction "PC9_PC9") (pintype "bidirectional"))
    )
    (net (code "42") (name "MR_PWM") (class "Default")
      (node (ref "IC2") (pin "15") (pinfunction "PWMB_15") (pintype "input"))
      (node (ref "U$6") (pin "PB15") (pinfunction "PB15_PB15") (pintype "bidirectional"))
    )
    (net (code "43") (name "Net-(D1-A)") (class "Default")
      (node (ref "D1") (pin "ANODA") (pinfunction "A_ANODA") (pintype "passive"))
      (node (ref "R6") (pin "1") (pinfunction "1_1") (pintype "passive"))
    )
    (net (code "44") (name "Net-(D1-C)") (class "Default")
      (node (ref "D1") (pin "KATODA") (pinfunction "C_KATODA") (pintype "passive"))
      (node (ref "IC1") (pin "16") (pinfunction "O1_16") (pintype "open_collector"))
    )
    (net (code "45") (name "Net-(D2-A)") (class "Default")
      (node (ref "D2") (pin "ANODA") (pinfunction "A_ANODA") (pintype "passive"))
      (node (ref "R15") (pin "1") (pinfunction "1_1") (pintype "passive"))
    )
    (net (code "46") (name "Net-(D2-C)") (class "Default")
      (node (ref "D2") (pin "KATODA") (pinfunction "C_KATODA") (pintype "passive"))
      (node (ref "IC1") (pin "15") (pinfunction "O2_15") (pintype "open_collector"))
    )
    (net (code "47") (name "Net-(D3-A)") (class "Default")
      (node (ref "D3") (pin "ANODA") (pinfunction "A_ANODA") (pintype "passive"))
      (node (ref "R22") (pin "1") (pinfunction "1_1") (pintype "passive"))
    )
    (net (code "48") (name "Net-(D3-C)") (class "Default")
      (node (ref "D3") (pin "KATODA") (pinfunction "C_KATODA") (pintype "passive"))
      (node (ref "IC1") (pin "14") (pinfunction "O3_14") (pintype "open_collector"))
    )
    (net (code "49") (name "Net-(D4-A)") (class "Default")
      (node (ref "D4") (pin "ANODA") (pinfunction "A_ANODA") (pintype "passive"))
      (node (ref "R7") (pin "1") (pinfunction "1_1") (pintype "passive"))
    )
    (net (code "50") (name "Net-(D4-C)") (class "Default")
      (node (ref "D4") (pin "KATODA") (pinfunction "C_KATODA") (pintype "passive"))
      (node (ref "IC1") (pin "13") (pinfunction "O4_13") (pintype "open_collector"))
    )
    (net (code "51") (name "Net-(D5-A)") (class "Default")
      (node (ref "D5") (pin "ANODA") (pinfunction "A_ANODA") (pintype "passive"))
      (node (ref "R8") (pin "1") (pinfunction "1_1") (pintype "passive"))
    )
    (net (code "52") (name "Net-(D5-C)") (class "Default")
      (node (ref "D5") (pin "KATODA") (pinfunction "C_KATODA") (pintype "passive"))
      (node (ref "IC1") (pin "11") (pinfunction "O6_11") (pintype "open_collector"))
    )
    (net (code "53") (name "Net-(D6-A)") (class "Default")
      (node (ref "D6") (pin "ANODA") (pinfunction "A_ANODA") (pintype "passive"))
      (node (ref "R5") (pin "1") (pinfunction "1_1") (pintype "passive"))
    )
    (net (code "54") (name "Net-(D6-C)") (class "Default")
      (node (ref "D6") (pin "KATODA") (pinfunction "C_KATODA") (pintype "passive"))
      (node (ref "IC1") (pin "10") (pinfunction "O7_10") (pintype "open_collector"))
    )
    (net (code "55") (name "Net-(FUSE-Pad2)") (class "Default")
      (node (ref "FUSE") (pin "2") (pinfunction "2_2") (pintype "passive"))
      (node (ref "FUSE1") (pin "2") (pinfunction "2_2") (pintype "passive"))
      (node (ref "U$3") (pin "3") (pinfunction "3_3") (pintype "bidirectional"))
      (node (ref "U$3") (pin "6") (pinfunction "6_6") (pintype "bidirectional"))
    )
    (net (code "56") (name "Net-(IC1-O5)") (class "Default")
      (node (ref "BUZ1") (pin "-") (pinfunction "-_-") (pintype "passive"))
      (node (ref "IC1") (pin "12") (pinfunction "O5_12") (pintype "open_collector"))
    )
    (net (code "57") (name "Net-(IC2-AO1')") (class "Default")
      (node (ref "IC2") (pin "1") (pinfunction "AO1_1") (pintype "output"))
      (node (ref "IC2") (pin "2") (pinfunction "AO1'_2") (pintype "output"))
      (node (ref "U$5") (pin "L_MOTOR_A") (pinfunction "L_MOTOR_A_L_MOTOR_A") (pintype "bidirectional"))
    )
    (net (code "58") (name "Net-(IC2-AO2')") (class "Default")
      (node (ref "IC2") (pin "5") (pinfunction "AO2_5") (pintype "output"))
      (node (ref "IC2") (pin "6") (pinfunction "AO2'_6") (pintype "output"))
      (node (ref "U$5") (pin "L_MOTOR_B") (pinfunction "L_MOTOR_B_L_MOTOR_B") (pintype "bidirectional"))
    )
    (net (code "59") (name "Net-(IC2-BO1')") (class "Default")
      (node (ref "IC2") (pin "11") (pinfunction "BO1_11") (pintype "output"))
      (node (ref "IC2") (pin "12") (pinfunction "BO1'_12") (pintype "output"))
      (node (ref "U$5") (pin "R_MOTOR_A") (pinfunction "R_MOTOR_A_R_MOTOR_A") (pintype "bidirectional"))
    )
    (net (code "60") (name "Net-(IC2-BO2')") (class "Default")
      (node (ref "IC2") (pin "7") (pinfunction "BO2_7") (pintype "output"))
      (node (ref "IC2") (pin "8") (pinfunction "BO2'_8") (pintype "output"))
      (node (ref "U$5") (pin "R_MOTOR_B") (pinfunction "R_MOTOR_B_R_MOTOR_B") (pintype "bidirectional"))
    )
    (net (code "61") (name "Net-(IC5-PadPWRGD)") (class "Default")
      (node (ref "IC5") (pin "PWRGD") (pinfunction "PWRGD_PWRGD") (pintype "bidirectional"))
      (node (ref "R16") (pin "1") (pinfunction "1_1") (pintype "passive"))
    )
    (net (code "62") (name "Net-(JP1-Pad2)") (class "Default")
      (node (ref "JP1") (pin "2") (pinfunction "2_2") (pintype "passive"))
      (node (ref "U$3") (pin "2") (pinfunction "2_2") (pintype "bidirectional"))
      (node (ref "U$3") (pin "5") (pinfunction "5_5") (pintype "bidirectional"))
    )
    (net (code "63") (name "Net-(LED1-PadA)") (class "Default")
      (node (ref "LED1") (pin "A") (pinfunction "A_A") (pintype "passive"))
      (node (ref "R12") (pin "1") (pinfunction "1_1") (pintype "passive"))
    )
    (net (code "64") (name "Net-(LED2-PadA)") (class "Default")
      (node (ref "LED2") (pin "A") (pinfunction "A_A") (pintype "passive"))
      (node (ref "R13") (pin "1") (pinfunction "1_1") (pintype "passive"))
    )
    (net (code "65") (name "Net-(LED3-PadA)") (class "Default")
      (node (ref "LED3") (pin "A") (pinfunction "A_A") (pintype "passive"))
      (node (ref "R10") (pin "1") (pinfunction "1_1") (pintype "passive"))
    )
    (net (code "66") (name "Net-(LED4-PadA)") (class "Default")
      (node (ref "LED4") (pin "A") (pinfunction "A_A") (pintype "passive"))
      (node (ref "R20") (pin "1") (pinfunction "1_1") (pintype "passive"))
    )
    (net (code "67") (name "Net-(LED6-PadA)") (class "Default")
      (node (ref "LED6") (pin "A") (pinfunction "A_A") (pintype "passive"))
      (node (ref "R27") (pin "1") (pinfunction "1_1") (pintype "passive"))
    )
    (net (code "68") (name "Net-(R11-Pad2)") (class "Default")
      (node (ref "R11") (pin "2") (pinfunction "2_2") (pintype "passive"))
      (node (ref "S2") (pin "2") (pinfunction "2_2") (pintype "passive"))
    )
    (net (code "69") (name "Net-(R18-Pad2)") (class "Default")
      (node (ref "R18") (pin "2") (pinfunction "2_2") (pintype "passive"))
      (node (ref "R19") (pin "2") (pinfunction "2_2") (pintype "passive"))
      (node (ref "S3") (pin "2") (pinfunction "2_2") (pintype "passive"))
    )
    (net (code "70") (name "Net-(R26-Pad1)") (class "Default")
      (node (ref "R26") (pin "1") (pinfunction "1_1") (pintype "passive"))
      (node (ref "SV1") (pin "6") (pinfunction "6_6") (pintype "passive"))
    )
    (net (code "71") (name "OSC_IN") (class "Default")
      (node (ref "C_OSC1") (pin "2") (pinfunction "2_2") (pintype "passive"))
      (node (ref "Q8") (pin "P$2") (pinfunction "2_P$2") (pintype "passive"))
      (node (ref "U$6") (pin "PH0") (pinfunction "PH0_PH0") (pintype "bidirectional"))
    )
    (net (code "72") (name "OSC_OUT") (class "Default")
      (node (ref "C_OSC2") (pin "2") (pinfunction "2_2") (pintype "passive"))
      (node (ref "Q8") (pin "P$1") (pinfunction "1_P$1") (pintype "passive"))
      (node (ref "U$6") (pin "PH1") (pinfunction "PH1_PH1") (pintype "bidirectional"))
    )
    (net (code "73") (name "RST") (class "Default")
      (node (ref "C2") (pin "1") (pinfunction "1_1") (pintype "passive"))
      (node (ref "R21") (pin "1") (pinfunction "1_1") (pintype "passive"))
      (node (ref "S5") (pin "2") (pinfunction "2_2") (pintype "passive"))
      (node (ref "U$6") (pin "NRST") (pinfunction "NRST_NRST") (pintype "bidirectional"))
    )
    (net (code "74") (name "SCLK") (class "Default")
      (node (ref "U$1") (pin "P$5") (pinfunction "CLK_P$5") (pintype "input"))
      (node (ref "U$6") (pin "PC10") (pinfunction "PC10_PC10") (pintype "bidirectional"))
    )
    (net (code "75") (name "SWCLK") (class "Default")
      (node (ref "SV1") (pin "7") (pinfunction "7_7") (pintype "passive"))
      (node (ref "U$6") (pin "PA14") (pinfunction "PA14_PA14") (pintype "bidirectional"))
    )
    (net (code "76") (name "SWDIO") (class "Default")
      (node (ref "SV1") (pin "5") (pinfunction "5_5") (pintype "passive"))
      (node (ref "U$6") (pin "PA13") (pinfunction "PA13_PA13") (pintype "bidirectional"))
    )
    (net (code "77") (name "VCAP_1") (class "Default")
      (node (ref "U$6") (pin "VCAP_1") (pinfunction "VCAP_1_VCAP_1") (pintype "bidirectional"))
      (node (ref "VCAP_1") (pin "1") (pinfunction "1_1") (pintype "passive"))
    )
    (net (code "78") (name "VCAP_2") (class "Default")
      (node (ref "U$6") (pin "VCAP_2") (pinfunction "VCAP_2_VCAP_2") (pintype "bidirectional"))
      (node (ref "VCAP_2") (pin "1") (pinfunction "1_1") (pintype "passive"))
    )
    (net (code "79") (name "unconnected-(C4-Pad+)") (class "Default")
      (node (ref "C4") (pin "+") (pinfunction "+_+") (pintype "passive"))
    )
    (net (code "80") (name "unconnected-(C4-Pad-)") (class "Default")
      (node (ref "C4") (pin "-") (pinfunction "-_-") (pintype "passive"))
    )
    (net (code "81") (name "unconnected-(U$3-Pad1)") (class "Default")
      (node (ref "U$3") (pin "1") (pinfunction "1_1") (pintype "bidirectional"))
    )
    (net (code "82") (name "unconnected-(U$3-Pad4)") (class "Default")
      (node (ref "U$3") (pin "4") (pinfunction "4_4") (pintype "bidirectional"))
    )
    (net (code "83") (name "unconnected-(U$6-PadPA4)") (class "Default")
      (node (ref "U$6") (pin "PA4") (pinfunction "PA4_PA4") (pintype "bidirectional"))
    )
    (net (code "84") (name "unconnected-(U$6-PadPA8)") (class "Default")
      (node (ref "U$6") (pin "PA8") (pinfunction "PA8_PA8") (pintype "bidirectional"))
    )
    (net (code "85") (name "unconnected-(U$6-PadPA11)") (class "Default")
      (node (ref "U$6") (pin "PA11") (pinfunction "PA11_PA11") (pintype "bidirectional"))
    )
    (net (code "86") (name "unconnected-(U$6-PadPA12)") (class "Default")
      (node (ref "U$6") (pin "PA12") (pinfunction "PA12_PA12") (pintype "bidirectional"))
    )
    (net (code "87") (name "unconnected-(U$6-PadPB10)") (class "Default")
      (node (ref "U$6") (pin "PB10") (pinfunction "PB10_PB10") (pintype "bidirectional"))
    )
    (net (code "88") (name "unconnected-(U$6-PadPB11)") (class "Default")
      (node (ref "U$6") (pin "PB11") (pinfunction "PB11_PB11") (pintype "bidirectional"))
    )
    (net (code "89") (name "unconnected-(U$6-PadPB12)") (class "Default")
      (node (ref "U$6") (pin "PB12") (pinfunction "PB12_PB12") (pintype "bidirectional"))
    )
    (net (code "90") (name "unconnected-(U$6-PadPB13)") (class "Default")
      (node (ref "U$6") (pin "PB13") (pinfunction "PB13_PB13") (pintype "bidirectional"))
    )
    (net (code "91") (name "unconnected-(U$6-PadPD2)") (class "Default")
      (node (ref "U$6") (pin "PD2") (pinfunction "PD2_PD2") (pintype "bidirectional"))
    )
  )
)
